# A-Power.net
KiCad netlist of a schematic drawn in Altium Designer
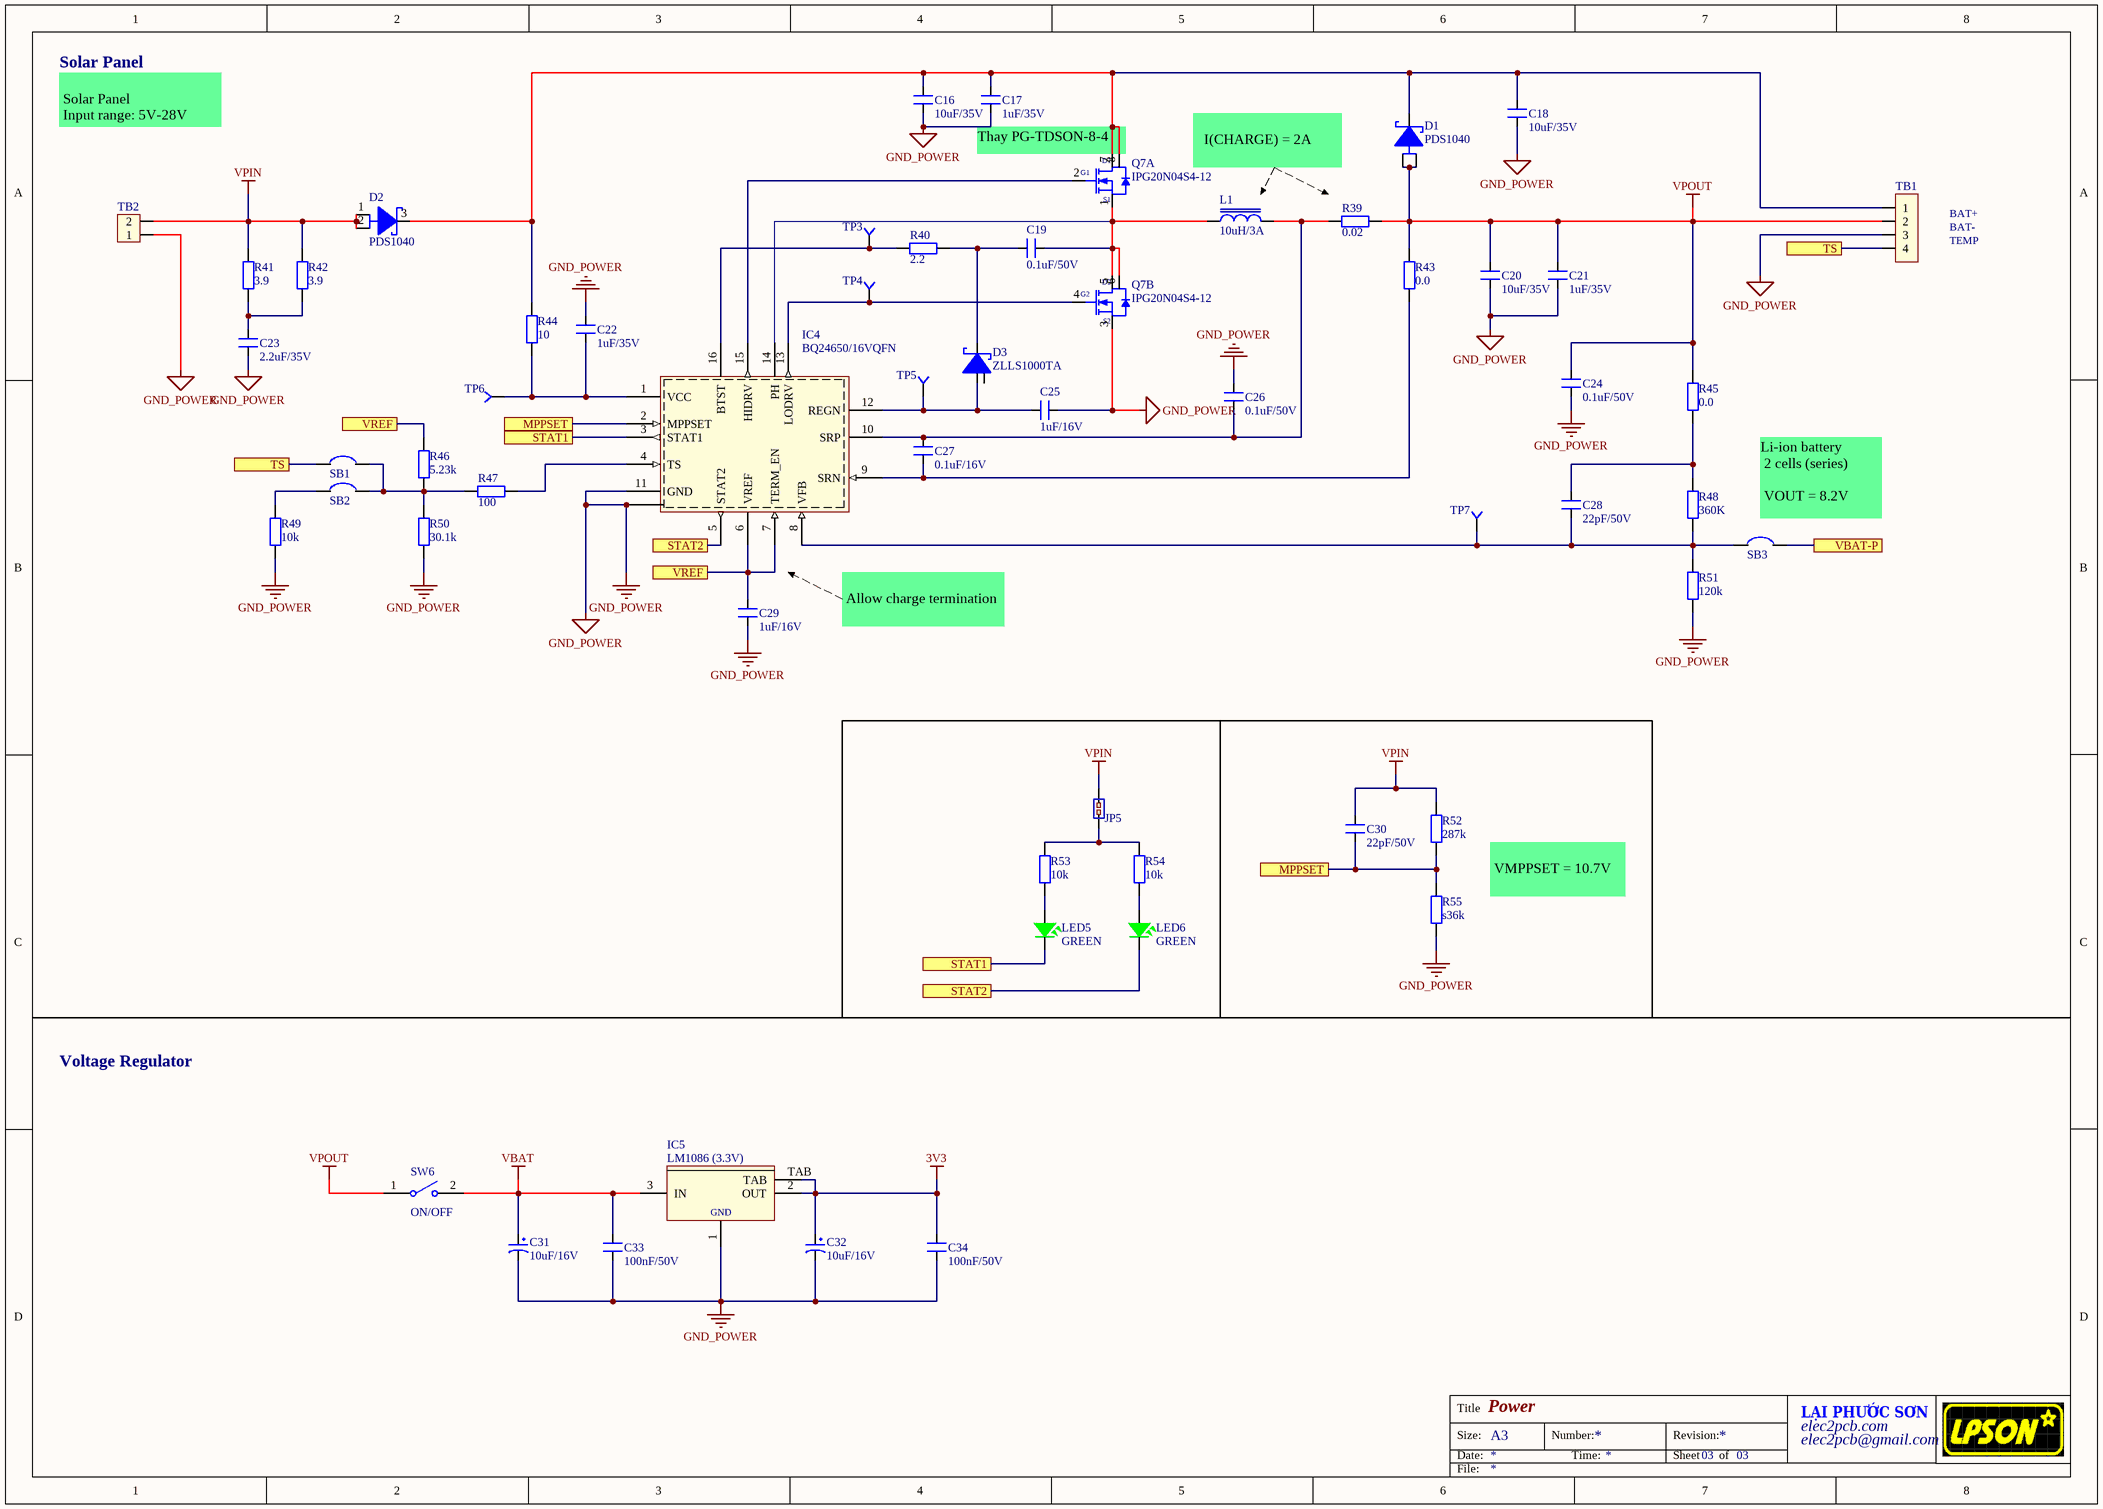
[diagram p0: A-Power.SchDoc]

(export (version "E")
  (design (tool "Eeschema 10.0.6"))
  (components
    (comp (ref "C16")
      (value "10uF/35V")
      (footprint "CAP_CERA_C3216(CC1206INCH)")
      (description "CAP CER 10UF 35V X7R 1206")
      (fields
        (field (name "MANUFACTURER") "Taiyo Yuden")
        (field (name "MANUFACTURER PART NUMBER") "GMK316AB7106KL-TR")
      )
      (libsource (lib "Tran Tuan") (part "CAP-CER/10uF/35V/X7R-1206"))
    )
    (comp (ref "C17")
      (value "1uF/35V")
      (footprint "CAP_CERA_C2012(CC0805INCH)")
      (description "CAP CER 1UF 35V X7R 0805")
      (fields
        (field (name "MANUFACTURER") "Taiyo Yuden")
        (field (name "MANUFACTURER PART NUMBER") "GMK212B7105KG-T")
      )
      (libsource (lib "Tran Tuan") (part "CAP-CER/1uF/35V/X7R/0805"))
    )
    (comp (ref "C18")
      (value "10uF/35V")
      (footprint "CAP_CERA_C3216(CC1206INCH)")
      (description "CAP CER 10UF 35V X7R 1206")
      (fields
        (field (name "MANUFACTURER") "Taiyo Yuden")
        (field (name "MANUFACTURER PART NUMBER") "GMK316AB7106KL-TR")
      )
      (libsource (lib "Tran Tuan") (part "CAP-CER/10uF/35V/X7R-1206"))
    )
    (comp (ref "C19")
      (value "0.1uF/50V")
      (footprint "CAP_CERA_C1608(CC0603INCH)")
      (description "CAP CER 0.1UF 50V X7R 0603")
      (fields
        (field (name "MANUFACTURER") "Kemet")
        (field (name "MANUFACTURER PART NUMBER") "C0603X104K5RACTU")
      )
      (libsource (lib "Tran Tuan") (part "CAP-CER/0.1uF/50V/X7R/0603"))
    )
    (comp (ref "C20")
      (value "10uF/35V")
      (footprint "CAP_CERA_C3216(CC1206INCH)")
      (description "CAP CER 10UF 35V X7R 1206")
      (fields
        (field (name "MANUFACTURER") "Taiyo Yuden")
        (field (name "MANUFACTURER PART NUMBER") "GMK316AB7106KL-TR")
      )
      (libsource (lib "Tran Tuan") (part "CAP-CER/10uF/35V/X7R-1206"))
    )
    (comp (ref "C21")
      (value "1uF/35V")
      (footprint "CAP_CERA_C2012(CC0805INCH)")
      (description "CAP CER 1UF 35V X7R 0805")
      (fields
        (field (name "MANUFACTURER") "Taiyo Yuden")
        (field (name "MANUFACTURER PART NUMBER") "GMK212B7105KG-T")
      )
      (libsource (lib "Tran Tuan") (part "CAP-CER/1uF/35V/X7R/0805"))
    )
    (comp (ref "C22")
      (value "1uF/35V")
      (footprint "CAP_CERA_C2012(CC0805INCH)")
      (description "CAP CER 1UF 35V X7R 0805")
      (fields
        (field (name "MANUFACTURER") "Taiyo Yuden")
        (field (name "MANUFACTURER PART NUMBER") "GMK212B7105KG-T")
      )
      (libsource (lib "Tran Tuan") (part "CAP-CER/1uF/35V/X7R/0805"))
    )
    (comp (ref "C23")
      (value "2.2uF/35V")
      (footprint "CAP_CERA_C3225(CC1210)")
      (description "CAP CER 2.2UF 35V X7R 1210")
      (fields
        (field (name "MANUFACTURER") "Taiyo Yuden")
        (field (name "MANUFACTURER PART NUMBER") "GMK325B7225KNHT")
      )
      (libsource (lib "Tran Tuan") (part "CAP-CER/2.2uF/35V/X7R/1210"))
    )
    (comp (ref "C24")
      (value "0.1uF/50V")
      (footprint "CAP_CERA_C1608(CC0603INCH)")
      (description "CAP CER 0.1UF 50V X7R 0603")
      (fields
        (field (name "MANUFACTURER") "Kemet")
        (field (name "MANUFACTURER PART NUMBER") "C0603X104K5RACTU")
      )
      (libsource (lib "Tran Tuan") (part "CAP-CER/0.1uF/50V/X7R/0603"))
    )
    (comp (ref "C25")
      (value "1uF/16V")
      (footprint "CAP_CERA_C2012(CC0805INCH)")
      (description "CAP CER 1UF 16V X7R 0805")
      (fields
        (field (name "MANUFACTURER") "Kemet")
        (field (name "MANUFACTURER PART NUMBER") "C0805C105K4RACTU")
      )
      (libsource (lib "Tran Tuan") (part "CAP-CER/1uF/16V/X7R/0805"))
    )
    (comp (ref "C26")
      (value "0.1uF/50V")
      (footprint "CAP_CERA_C1608(CC0603INCH)")
      (description "CAP CER 0.1UF 50V X7R 0603")
      (fields
        (field (name "MANUFACTURER") "Kemet")
        (field (name "MANUFACTURER PART NUMBER") "C0603X104K5RACTU")
      )
      (libsource (lib "Tran Tuan") (part "CAP-CER/0.1uF/50V/X7R/0603"))
    )
    (comp (ref "C27")
      (value "0.1uF/16V")
      (footprint "CAP_CERA_C1608(CC0603INCH)")
      (description "CAP CER 0.1UF 16V X7R 0603")
      (fields
        (field (name "MANUFACTURER") "Yageo")
        (field (name "MANUFACTURER PART NUMBER") "CC0603KRX7R7BB104")
      )
      (libsource (lib "Tran Tuan") (part "CAP-CER/0.1uF/16V/X7R/0603"))
    )
    (comp (ref "C28")
      (value "22pF/50V")
      (footprint "CAP_CERA_C1608(CC0603INCH)")
      (description "CAP CER 22PF 50V X7R 0603")
      (fields
        (field (name "MANUFACTURER") "AVX Corporation")
        (field (name "MANUFACTURER PART NUMBER") "06035C220JAT2A")
      )
      (libsource (lib "Tran Tuan") (part "CAP-CER/22pF/50V/X7R/0603"))
    )
    (comp (ref "C29")
      (value "1uF/16V")
      (footprint "CAP_CERA_C2012(CC0805INCH)")
      (description "CAP CER 1UF 16V X7R 0805")
      (fields
        (field (name "MANUFACTURER") "Kemet")
        (field (name "MANUFACTURER PART NUMBER") "C0805C105K4RACTU")
      )
      (libsource (lib "Tran Tuan") (part "CAP-CER/1uF/16V/X7R/0805"))
    )
    (comp (ref "C30")
      (value "22pF/50V")
      (footprint "CAP_CERA_C1608(CC0603INCH)")
      (description "CAP CER 22PF 50V X7R 0603")
      (fields
        (field (name "MANUFACTURER") "AVX Corporation")
        (field (name "MANUFACTURER PART NUMBER") "06035C220JAT2A")
      )
      (libsource (lib "Tran Tuan") (part "CAP-CER/22pF/50V/X7R/0603"))
    )
    (comp (ref "C31")
      (value "10uF/16V")
      (footprint "CAP_CERA_C3216(CC1206INCH)")
      (description "CAP TANT 10UF 16V 10% 1206")
      (fields
        (field (name "MANUFACTURER") "Kemet")
        (field (name "MANUFACTURER PART NUMBER") "T491A106K016AT")
      )
      (libsource (lib "Tran Tuan") (part "CAP-TANT/10uF/16V/1206"))
    )
    (comp (ref "C32")
      (value "10uF/16V")
      (footprint "CAP_CERA_C3216(CC1206INCH)")
      (description "CAP TANT 10UF 16V 10% 1206")
      (fields
        (field (name "MANUFACTURER") "Kemet")
        (field (name "MANUFACTURER PART NUMBER") "T491A106K016AT")
      )
      (libsource (lib "Tran Tuan") (part "CAP-TANT/10uF/16V/1206"))
    )
    (comp (ref "C33")
      (value "100nF/50V")
      (footprint "CAP_CERA_C2012(CC0805INCH)")
      (description "CAP CER 0.1UF 50V X7R 0805")
      (fields
        (field (name "MANUFACTURER") "AVX Corporation")
        (field (name "MANUFACTURER PART NUMBER") "08055C104KAT2A")
      )
      (libsource (lib "Tran Tuan") (part "CAP-CER/100nF/50V/X7R-0805"))
    )
    (comp (ref "C34")
      (value "100nF/50V")
      (footprint "CAP_CERA_C2012(CC0805INCH)")
      (description "CAP CER 0.1UF 50V X7R 0805")
      (fields
        (field (name "MANUFACTURER") "AVX Corporation")
        (field (name "MANUFACTURER PART NUMBER") "08055C104KAT2A")
      )
      (libsource (lib "Tran Tuan") (part "CAP-CER/100nF/50V/X7R-0805"))
    )
    (comp (ref "D1")
      (value "PDS1040")
      (footprint "PDS1040")
      (description "DIODE SCHOTTKY 40V 10A POWERDI5")
      (fields
        (field (name "MANUFACTURER") "Diodes Incorporated")
        (field (name "MANUFACTURER PART NUMBER") "PDS1040-13")
      )
      (libsource (lib "Tran Tuan") (part "DIODE-PDS1040/POWERDI5"))
    )
    (comp (ref "D2")
      (value "PDS1040")
      (footprint "PDS1040")
      (description "DIODE SCHOTTKY 40V 10A POWERDI5")
      (fields
        (field (name "MANUFACTURER") "Diodes Incorporated")
        (field (name "MANUFACTURER PART NUMBER") "PDS1040-13")
      )
      (libsource (lib "") (part "DIODE-PDS1040/POWERDI5_1"))
    )
    (comp (ref "D3")
      (value "ZLLS1000TA")
      (footprint "ZLLS1000")
      (description "DIODE SCHOTTKY 40V 1.16A SOT23-3")
      (fields (field (name "MANUFACTURER") "Diodes Incorporated"))
      (libsource (lib "Tran Tuan") (part "DIODE-ZLLS1000TA/SOT23-3"))
    )
    (comp (ref "IC4")
      (value "BQ24650/16VQFN")
      (footprint "BQ24650-16VQFN")
      (description "IC SYNC SW-MODE BAT CHRGR 16VQFN")
      (fields
        (field (name "MANUFACTURER") "Texas Instruments")
        (field (name "MANUFACTURER PART NUMBER") "BQ24650RVAT")
      )
      (libsource (lib "Tran Tuan") (part "BQ24650/16VQFN"))
    )
    (comp (ref "IC5")
      (value "LM1086 (3.3V)")
      (footprint "LM1086")
      (description "IC REG LDO 3.3V 1.5A DDPAK")
      (fields
        (field (name "MANUFACTURER") "Texas Instruments")
        (field (name "MANUFACTURER PART NUMBER") "LM1086CS-3.3/NOPB")
      )
      (libsource (lib "Tran Tuan") (part "LM1086CS-3.3/NOPB"))
    )
    (comp (ref "JP5")
      (value "JP2-ShortingJumper")
      (footprint "Header_2")
      (description "2.54mm 2-Pin Shorting Jumper")
      (libsource (lib "Tran Tuan") (part "JP2-ShortingJumper"))
    )
    (comp (ref "L1")
      (value "10uH/3A")
      (footprint "IHLP-2525CZ-01")
      (description "FIXED IND 10UH 3A 105mOHM SMD")
      (fields
        (field (name "MANUFACTURER") "Vishay Dale")
        (field (name "MANUFACTURER PART NUMBER") "IHLP2525CZER100M01")
      )
      (libsource (lib "Tran Tuan") (part "IND-10uH/3A/105mOHM"))
    )
    (comp (ref "LED5")
      (value "GREEN")
      (footprint "Led 0805G")
      (description "LED GREEN CLEAR 0805 SMD")
      (fields
        (field (name "MANUFACTURER") "Lite-On Inc.")
        (field (name "MANUFACTURER PART NUMBER") "LTST-C171GKT")
      )
      (libsource (lib "Tran Tuan") (part "LED-GREEN/CLEAR/0805"))
    )
    (comp (ref "LED6")
      (value "GREEN")
      (footprint "Led 0805G")
      (description "LED GREEN CLEAR 0805 SMD")
      (fields
        (field (name "MANUFACTURER") "Lite-On Inc.")
        (field (name "MANUFACTURER PART NUMBER") "LTST-C171GKT")
      )
      (libsource (lib "Tran Tuan") (part "LED-GREEN/CLEAR/0805"))
    )
    (comp (ref "Q7")
      (value "IPG20N04S4-12")
      (footprint "PG-TDSON-8-4")
      (description "MOSFE,T 2N-CH, 40V 20A TDSON-8 OptiMOS-T2")
      (fields (field (name "MANUFACTURER") "Infineon"))
      (libsource (lib "Tran Tuan") (part "MOSFET-IPG20N04S4/TDSON8"))
    )
    (comp (ref "R39")
      (value "~")
      (footprint "RES-1206-3216MM")
      (description "RES SMD 0.02 OHM 1% 1W 1206")
      (fields
        (field (name "MANUFACTURER") "Vishay Dale")
        (field (name "MANUFACTURER PART NUMBER") "WSLP1206R0200FEA")
        (field (name "RESISTANCE (OHMS)") "0.02")
      )
      (libsource (lib "Tran Tuan") (part "RES-1206/±1%"))
    )
    (comp (ref "R40")
      (value "~")
      (footprint "RESC2012(0805)")
      (description "RES SMD 2.2 OHM 5% 1/8W 0805")
      (fields
        (field (name "MANUFACTURER") "Panasonic Electronic Components")
        (field (name "MANUFACTURER PART NUMBER") "ERJ-6GEYJ2R2V")
        (field (name "RESISTANCE (OHMS)") "2.2")
      )
      (libsource (lib "Tran Tuan") (part "RES-0805/±5%"))
    )
    (comp (ref "R41")
      (value "~")
      (footprint "RES-1206-3216MM")
      (description "RES SMD 3.9 OHM 1% 1/4W 1206")
      (fields
        (field (name "MANUFACTURER") "Panasonic Electronic Components")
        (field (name "MANUFACTURER PART NUMBER") "ERJ-8RQF3R9V")
        (field (name "RESISTANCE (OHMS)") "3.9")
      )
      (libsource (lib "Tran Tuan") (part "RES-1206/±5%"))
    )
    (comp (ref "R42")
      (value "~")
      (footprint "RES-1206-3216MM")
      (description "RES SMD 3.9 OHM 1% 1/4W 1206")
      (fields
        (field (name "MANUFACTURER") "Panasonic Electronic Components")
        (field (name "MANUFACTURER PART NUMBER") "ERJ-8RQF3R9V")
        (field (name "RESISTANCE (OHMS)") "3.9")
      )
      (libsource (lib "Tran Tuan") (part "RES-1206/±5%"))
    )
    (comp (ref "R43")
      (value "~")
      (footprint "RESC2012(0805)")
      (description "RES SMD 0.0 OHM JUMPER 1/8W 0805")
      (fields
        (field (name "MANUFACTURER") "Yageo")
        (field (name "MANUFACTURER PART NUMBER") "RC0805JR-070RL")
        (field (name "RESISTANCE (OHMS)") "0.0")
      )
      (libsource (lib "") (part "RES-0805/±5%_1"))
    )
    (comp (ref "R44")
      (value "~")
      (footprint "RESC2012(0805)")
      (description "RES SMD 10 OHM 5% 1/8W 0805")
      (fields
        (field (name "MANUFACTURER") "Yageo")
        (field (name "MANUFACTURER PART NUMBER") "RC0805JR-0710RL")
        (field (name "RESISTANCE (OHMS)") "10")
      )
      (libsource (lib "") (part "RES-0805/±5%_1"))
    )
    (comp (ref "R45")
      (value "~")
      (footprint "RESC2012(0805)")
      (description "RES SMD 0.0 OHM JUMPER 1/8W 0805")
      (fields
        (field (name "MANUFACTURER") "Yageo")
        (field (name "MANUFACTURER PART NUMBER") "RC0805JR-070RL")
        (field (name "RESISTANCE (OHMS)") "0.0")
      )
      (libsource (lib "") (part "RES-0805/±5%_1"))
    )
    (comp (ref "R46")
      (value "~")
      (footprint "RESC2012(0805)")
      (description "RES SMD 5.23K OHM 1% 1/8W 0805")
      (fields
        (field (name "MANUFACTURER") "Panasonic Electronic Components")
        (field (name "MANUFACTURER PART NUMBER") "ERJ-6ENF5231V")
        (field (name "RESISTANCE (OHMS)") "5.23k")
      )
      (libsource (lib "Tran Tuan") (part "RES-0805/±1%"))
    )
    (comp (ref "R47")
      (value "~")
      (footprint "RESC2012(0805)")
      (description "RES SMD 100 OHM 5% 1/8W 0805")
      (fields
        (field (name "MANUFACTURER") "Panasonic Electronic Components")
        (field (name "MANUFACTURER PART NUMBER") "ERJ-6GEYJ101V")
        (field (name "RESISTANCE (OHMS)") "100")
      )
      (libsource (lib "Tran Tuan") (part "RES-0805/±5%"))
    )
    (comp (ref "R48")
      (value "360K")
      (footprint "RESC2012(0805)")
      (description "RES SMD 360K OHM 1% 1/8W 0805")
      (fields
        (field (name "MANUFACTURER") "Yageo")
        (field (name "MANUFACTURER PART NUMBER") "RC0805FR-07360KL")
      )
      (libsource (lib "") (part "RES-0805/±1%_1"))
    )
    (comp (ref "R49")
      (value "~")
      (footprint "RESC2012(0805)")
      (description "RES SMD 10K OHM 5% 1/8W 0805")
      (fields
        (field (name "MANUFACTURER") "Yageo")
        (field (name "MANUFACTURER PART NUMBER") "RC0805JR-0710KL")
        (field (name "RESISTANCE (OHMS)") "10k")
      )
      (libsource (lib "") (part "RES-0805/±5%_1"))
    )
    (comp (ref "R50")
      (value "~")
      (footprint "RESC2012(0805)")
      (description "RES SMD 30.1K OHM 1% 1/8W 0805")
      (fields
        (field (name "MANUFACTURER") "Yageo")
        (field (name "MANUFACTURER PART NUMBER") "RC0805FR-0730K1L")
        (field (name "RESISTANCE (OHMS)") "30.1k")
      )
      (libsource (lib "Tran Tuan") (part "RES-0805/±1%"))
    )
    (comp (ref "R51")
      (value "~")
      (footprint "RESC2012(0805)")
      (description "RES SMD 120K OHM 1% 1/8W 0805")
      (fields
        (field (name "MANUFACTURER") "Yageo")
        (field (name "MANUFACTURER PART NUMBER") "RC0805FR-07120KL")
        (field (name "RESISTANCE (OHMS)") "120k")
      )
      (libsource (lib "Tran Tuan") (part "RES-0805/±1%"))
    )
    (comp (ref "R52")
      (value "~")
      (footprint "RESC2012(0805)")
      (description "RES SMD 287K OHM 1% 1/8W 0805")
      (fields
        (field (name "MANUFACTURER") "Panasonic Electronic Components")
        (field (name "MANUFACTURER PART NUMBER") "ERJ-6ENF2873V")
        (field (name "RESISTANCE (OHMS)") "287k")
      )
      (libsource (lib "Tran Tuan") (part "RES-0805/±1%"))
    )
    (comp (ref "R53")
      (value "~")
      (footprint "RESC2012(0805)")
      (description "RES SMD 10K OHM 5% 1/8W 0805")
      (fields
        (field (name "MANUFACTURER") "Yageo")
        (field (name "MANUFACTURER PART NUMBER") "RC0805JR-0710KL")
        (field (name "RESISTANCE (OHMS)") "10k")
      )
      (libsource (lib "") (part "RES-0805/±5%_1"))
    )
    (comp (ref "R54")
      (value "~")
      (footprint "RESC2012(0805)")
      (description "RES SMD 10K OHM 5% 1/8W 0805")
      (fields
        (field (name "MANUFACTURER") "Yageo")
        (field (name "MANUFACTURER PART NUMBER") "RC0805JR-0710KL")
        (field (name "RESISTANCE (OHMS)") "10k")
      )
      (libsource (lib "") (part "RES-0805/±5%_1"))
    )
    (comp (ref "R55")
      (value "~")
      (footprint "RESC2012(0805)")
      (description "RES SMD 36K OHM 1% 1/8W 0805")
      (fields
        (field (name "MANUFACTURER") "Panasonic Electronic Components")
        (field (name "MANUFACTURER PART NUMBER") "ERJ-6ENF3602V")
        (field (name "RESISTANCE (OHMS)") "s36k")
      )
      (libsource (lib "") (part "RES-0805/±1%_1"))
    )
    (comp (ref "SB1")
      (value "Connect")
      (footprint "head PAD")
      (description "Jumper, Connector, 2-pad")
      (libsource (lib "Tran Tuan") (part "Connector-SB"))
    )
    (comp (ref "SB2")
      (value "Connect")
      (footprint "head PAD")
      (description "Jumper, Connector, 2-pad")
      (libsource (lib "Tran Tuan") (part "Connector-SB"))
    )
    (comp (ref "SB3")
      (value "Connect")
      (footprint "head PAD")
      (description "Jumper, Connector, 2-pad")
      (libsource (lib "Tran Tuan") (part "Connector-SB"))
    )
    (comp (ref "SW6")
      (value "ON/OFF")
      (footprint "SW-POWER")
      (description "SWITCH ROCKER SPST 16A 125V")
      (fields
        (field (name "MANUFACTURER") "TE Connectivity Alcoswitch Switches")
        (field (name "MANUFACTURER PART NUMBER") "PRASA1-16F-BB0BW")
      )
      (libsource (lib "Tran Tuan") (part "SW-ROCKER/SPST/16A"))
    )
    (comp (ref "TB1")
      (value "TERM BLOCK")
      (footprint "MKDS-DOMINO-4-PIN")
      (description "TERM BLOCK 4POS 3.81MM PCB GRN")
      (fields
        (field (name "MANUFACTURER") "Phoenix Contact")
        (field (name "MANUFACTURER PART NUMBER") "1727036")
      )
      (libsource (lib "Tran Tuan") (part "TERM/3.81MM/4POS/GREEN"))
    )
    (comp (ref "TB2")
      (value "TERM BLOCK")
      (footprint "MKDS-DOMINO-2-PIN")
      (description "TERM BLOCK 2POS 3.81MM PCB GRN")
      (fields
        (field (name "MANUFACTURER") "Phoenix Contact")
        (field (name "MANUFACTURER PART NUMBER") "1727010")
      )
      (libsource (lib "Tran Tuan") (part "TERM/3.81MM/2POS/GREEN"))
    )
    (comp (ref "TP3")
      (value "Test Point")
      (footprint "Test_point_VIA06")
      (description "Test Point, Pad, Hole")
      (libsource (lib "Tran Tuan") (part "Connector-TP"))
    )
    (comp (ref "TP4")
      (value "Test Point")
      (footprint "Test_point_VIA06")
      (description "Test Point, Pad, Hole")
      (libsource (lib "Tran Tuan") (part "Connector-TP"))
    )
    (comp (ref "TP5")
      (value "Test Point")
      (footprint "Test_point_VIA06")
      (description "Test Point, Pad, Hole")
      (libsource (lib "Tran Tuan") (part "Connector-TP"))
    )
    (comp (ref "TP6")
      (value "Test Point")
      (footprint "Test_point_VIA06")
      (description "Test Point, Pad, Hole")
      (libsource (lib "Tran Tuan") (part "Connector-TP"))
    )
    (comp (ref "TP7")
      (value "Test Point")
      (footprint "Test_point_VIA06")
      (description "Test Point, Pad, Hole")
      (libsource (lib "Tran Tuan") (part "Connector-TP"))
    )
  )
  (nets
    (net (code "1") (name "/MPPSET") (class "Default")
      (node (ref "C30") (pin "2") (pinfunction "2_2") (pintype "passive"))
      (node (ref "IC4") (pin "2") (pinfunction "MPPSET_2") (pintype "input"))
      (node (ref "R52") (pin "2") (pinfunction "2_2") (pintype "passive"))
      (node (ref "R55") (pin "2") (pinfunction "2_2") (pintype "passive"))
    )
    (net (code "2") (name "/STAT1") (class "Default")
      (node (ref "IC4") (pin "3") (pinfunction "STAT1_3") (pintype "output"))
      (node (ref "LED5") (pin "2") (pinfunction "K_2") (pintype "passive"))
    )
    (net (code "3") (name "/STAT2") (class "Default")
      (node (ref "IC4") (pin "5") (pinfunction "STAT2_5") (pintype "output"))
      (node (ref "LED6") (pin "2") (pinfunction "K_2") (pintype "passive"))
    )
    (net (code "4") (name "/TS") (class "Default")
      (node (ref "SB1") (pin "2") (pinfunction "2_2") (pintype "passive"))
      (node (ref "TB1") (pin "4") (pinfunction "4_4") (pintype "passive"))
    )
    (net (code "5") (name "/VBAT-P") (class "Default")
      (node (ref "SB3") (pin "1") (pinfunction "1_1") (pintype "passive"))
    )
    (net (code "6") (name "/VREF") (class "Default")
      (node (ref "C29") (pin "2") (pinfunction "2_2") (pintype "passive"))
      (node (ref "IC4") (pin "6") (pinfunction "VREF_6") (pintype "power_in"))
      (node (ref "IC4") (pin "7") (pinfunction "TERM_EN_7") (pintype "input"))
      (node (ref "R46") (pin "1") (pinfunction "1_1") (pintype "passive"))
    )
    (net (code "7") (name "3V3") (class "Default")
      (node (ref "C32") (pin "1") (pinfunction "1_1") (pintype "passive"))
      (node (ref "C34") (pin "1") (pinfunction "1_1") (pintype "passive"))
      (node (ref "IC5") (pin "2") (pinfunction "OUT_2") (pintype "power_in"))
      (node (ref "IC5") (pin "TAB") (pinfunction "TAB_TAB") (pintype "power_in"))
    )
    (net (code "8") (name "GND_POWER") (class "Default")
      (node (ref "C16") (pin "2") (pinfunction "2_2") (pintype "passive"))
      (node (ref "C17") (pin "2") (pinfunction "2_2") (pintype "passive"))
      (node (ref "C18") (pin "2") (pinfunction "2_2") (pintype "passive"))
      (node (ref "C20") (pin "2") (pinfunction "2_2") (pintype "passive"))
      (node (ref "C21") (pin "2") (pinfunction "2_2") (pintype "passive"))
      (node (ref "C22") (pin "2") (pinfunction "2_2") (pintype "passive"))
      (node (ref "C23") (pin "2") (pinfunction "2_2") (pintype "passive"))
      (node (ref "C24") (pin "1") (pinfunction "1_1") (pintype "passive"))
      (node (ref "C25") (pin "1") (pinfunction "1_1") (pintype "passive"))
      (node (ref "C26") (pin "2") (pinfunction "2_2") (pintype "passive"))
      (node (ref "C29") (pin "1") (pinfunction "1_1") (pintype "passive"))
      (node (ref "C31") (pin "2") (pinfunction "2_2") (pintype "passive"))
      (node (ref "C32") (pin "2") (pinfunction "2_2") (pintype "passive"))
      (node (ref "C33") (pin "2") (pinfunction "2_2") (pintype "passive"))
      (node (ref "C34") (pin "2") (pinfunction "2_2") (pintype "passive"))
      (node (ref "IC4") (pin "11") (pinfunction "GND_11") (pintype "power_in"))
      (node (ref "IC4") (pin "PAD") (pinfunction "PAD_PAD") (pintype "power_in"))
      (node (ref "IC5") (pin "1") (pinfunction "GND_1") (pintype "power_in"))
      (node (ref "Q7") (pin "3") (pinfunction "S2_3") (pintype "passive"))
      (node (ref "R49") (pin "2") (pinfunction "2_2") (pintype "passive"))
      (node (ref "R50") (pin "2") (pinfunction "2_2") (pintype "passive"))
      (node (ref "R51") (pin "2") (pinfunction "2_2") (pintype "passive"))
      (node (ref "R55") (pin "1") (pinfunction "1_1") (pintype "passive"))
      (node (ref "TB1") (pin "3") (pinfunction "3_3") (pintype "passive"))
      (node (ref "TB2") (pin "1") (pinfunction "1_1") (pintype "passive"))
    )
    (net (code "9") (name "Net-(C23-Pad1)") (class "Default")
      (node (ref "C23") (pin "1") (pinfunction "1_1") (pintype "passive"))
      (node (ref "R41") (pin "2") (pinfunction "2_2") (pintype "passive"))
      (node (ref "R42") (pin "2") (pinfunction "2_2") (pintype "passive"))
    )
    (net (code "10") (name "Net-(C28-Pad1)") (class "Default")
      (node (ref "C28") (pin "1") (pinfunction "1_1") (pintype "passive"))
      (node (ref "R45") (pin "2") (pinfunction "2_2") (pintype "passive"))
      (node (ref "R48") (pin "2") (pinfunction "2_2") (pintype "passive"))
    )
    (net (code "11") (name "Net-(D1-K)") (class "Default")
      (node (ref "C16") (pin "1") (pinfunction "1_1") (pintype "passive"))
      (node (ref "C17") (pin "1") (pinfunction "1_1") (pintype "passive"))
      (node (ref "C18") (pin "1") (pinfunction "1_1") (pintype "passive"))
      (node (ref "D1") (pin "3") (pinfunction "K_3") (pintype "passive"))
      (node (ref "D2") (pin "3") (pinfunction "K_3") (pintype "passive"))
      (node (ref "Q7") (pin "7") (pinfunction "D1_7") (pintype "passive"))
      (node (ref "Q7") (pin "8") (pinfunction "D1_8") (pintype "passive"))
      (node (ref "R44") (pin "1") (pinfunction "1_1") (pintype "passive"))
      (node (ref "TB1") (pin "1") (pinfunction "1_1") (pintype "passive"))
    )
    (net (code "12") (name "Net-(D3-A)") (class "Default")
      (node (ref "C25") (pin "2") (pinfunction "2_2") (pintype "passive"))
      (node (ref "D3") (pin "1") (pinfunction "A_1") (pintype "passive"))
      (node (ref "IC4") (pin "12") (pinfunction "REGN_12") (pintype "power_in"))
      (node (ref "TP5") (pin "1") (pinfunction "1_1") (pintype "passive"))
    )
    (net (code "13") (name "Net-(D3-K)") (class "Default")
      (node (ref "C19") (pin "1") (pinfunction "1_1") (pintype "passive"))
      (node (ref "D3") (pin "3") (pinfunction "K_3") (pintype "passive"))
      (node (ref "R40") (pin "2") (pinfunction "2_2") (pintype "passive"))
    )
    (net (code "14") (name "Net-(IC4-BTST)") (class "Default")
      (node (ref "IC4") (pin "16") (pinfunction "BTST_16") (pintype "power_in"))
      (node (ref "R40") (pin "1") (pinfunction "1_1") (pintype "passive"))
      (node (ref "TP3") (pin "1") (pinfunction "1_1") (pintype "passive"))
    )
    (net (code "15") (name "Net-(IC4-HIDRV)") (class "Default")
      (node (ref "IC4") (pin "15") (pinfunction "HIDRV_15") (pintype "output"))
      (node (ref "Q7") (pin "2") (pinfunction "G1_2") (pintype "passive"))
    )
    (net (code "16") (name "Net-(IC4-LODRV)") (class "Default")
      (node (ref "IC4") (pin "13") (pinfunction "LODRV_13") (pintype "output"))
      (node (ref "Q7") (pin "4") (pinfunction "G2_4") (pintype "passive"))
      (node (ref "TP4") (pin "1") (pinfunction "1_1") (pintype "passive"))
    )
    (net (code "17") (name "Net-(IC4-PH)") (class "Default")
      (node (ref "C19") (pin "2") (pinfunction "2_2") (pintype "passive"))
      (node (ref "IC4") (pin "14") (pinfunction "PH_14") (pintype "power_in"))
      (node (ref "L1") (pin "1") (pinfunction "1_1") (pintype "passive"))
      (node (ref "Q7") (pin "1") (pinfunction "S1_1") (pintype "passive"))
      (node (ref "Q7") (pin "5") (pinfunction "D2_5") (pintype "passive"))
      (node (ref "Q7") (pin "6") (pinfunction "D2_6") (pintype "passive"))
    )
    (net (code "18") (name "Net-(IC4-SRN)") (class "Default")
      (node (ref "C27") (pin "2") (pinfunction "2_2") (pintype "passive"))
      (node (ref "IC4") (pin "9") (pinfunction "SRN_9") (pintype "input"))
      (node (ref "R43") (pin "2") (pinfunction "2_2") (pintype "passive"))
    )
    (net (code "19") (name "Net-(IC4-SRP)") (class "Default")
      (node (ref "C26") (pin "1") (pinfunction "1_1") (pintype "passive"))
      (node (ref "C27") (pin "1") (pinfunction "1_1") (pintype "passive"))
      (node (ref "IC4") (pin "10") (pinfunction "SRP_10") (pintype "passive"))
      (node (ref "L1") (pin "2") (pinfunction "2_2") (pintype "passive"))
      (node (ref "R39") (pin "1") (pinfunction "1_1") (pintype "passive"))
    )
    (net (code "20") (name "Net-(IC4-TS)") (class "Default")
      (node (ref "IC4") (pin "4") (pinfunction "TS_4") (pintype "input"))
      (node (ref "R47") (pin "2") (pinfunction "2_2") (pintype "passive"))
    )
    (net (code "21") (name "Net-(IC4-VCC)") (class "Default")
      (node (ref "C22") (pin "1") (pinfunction "1_1") (pintype "passive"))
      (node (ref "IC4") (pin "1") (pinfunction "VCC_1") (pintype "power_in"))
      (node (ref "R44") (pin "2") (pinfunction "2_2") (pintype "passive"))
      (node (ref "TP6") (pin "1") (pinfunction "1_1") (pintype "passive"))
    )
    (net (code "22") (name "Net-(IC4-VFB)") (class "Default")
      (node (ref "C28") (pin "2") (pinfunction "2_2") (pintype "passive"))
      (node (ref "IC4") (pin "8") (pinfunction "VFB_8") (pintype "input"))
      (node (ref "R48") (pin "1") (pinfunction "1_1") (pintype "passive"))
      (node (ref "R51") (pin "1") (pinfunction "1_1") (pintype "passive"))
      (node (ref "SB3") (pin "2") (pinfunction "2_2") (pintype "passive"))
      (node (ref "TP7") (pin "1") (pinfunction "1_1") (pintype "passive"))
    )
    (net (code "23") (name "Net-(JP5-Pad1)") (class "Default")
      (node (ref "JP5") (pin "1") (pinfunction "1_1") (pintype "passive"))
      (node (ref "R53") (pin "1") (pinfunction "1_1") (pintype "passive"))
      (node (ref "R54") (pin "1") (pinfunction "1_1") (pintype "passive"))
    )
    (net (code "24") (name "Net-(LED5-A)") (class "Default")
      (node (ref "LED5") (pin "1") (pinfunction "A_1") (pintype "passive"))
      (node (ref "R53") (pin "2") (pinfunction "2_2") (pintype "passive"))
    )
    (net (code "25") (name "Net-(LED6-A)") (class "Default")
      (node (ref "LED6") (pin "1") (pinfunction "A_1") (pintype "passive"))
      (node (ref "R54") (pin "2") (pinfunction "2_2") (pintype "passive"))
    )
    (net (code "26") (name "Net-(R46-Pad2)") (class "Default")
      (node (ref "R46") (pin "2") (pinfunction "2_2") (pintype "passive"))
      (node (ref "R47") (pin "1") (pinfunction "1_1") (pintype "passive"))
      (node (ref "R50") (pin "1") (pinfunction "1_1") (pintype "passive"))
      (node (ref "SB1") (pin "1") (pinfunction "1_1") (pintype "passive"))
      (node (ref "SB2") (pin "1") (pinfunction "1_1") (pintype "passive"))
    )
    (net (code "27") (name "Net-(R49-Pad1)") (class "Default")
      (node (ref "R49") (pin "1") (pinfunction "1_1") (pintype "passive"))
      (node (ref "SB2") (pin "2") (pinfunction "2_2") (pintype "passive"))
    )
    (net (code "28") (name "VBAT") (class "Default")
      (node (ref "C31") (pin "1") (pinfunction "1_1") (pintype "passive"))
      (node (ref "C33") (pin "1") (pinfunction "1_1") (pintype "passive"))
      (node (ref "IC5") (pin "3") (pinfunction "IN_3") (pintype "power_in"))
      (node (ref "SW6") (pin "2") (pinfunction "2_2") (pintype "passive"))
    )
    (net (code "29") (name "VPIN") (class "Default")
      (node (ref "C30") (pin "1") (pinfunction "1_1") (pintype "passive"))
      (node (ref "D2") (pin "1") (pinfunction "A1_1") (pintype "passive"))
      (node (ref "D2") (pin "2") (pinfunction "A2_2") (pintype "passive"))
      (node (ref "JP5") (pin "2") (pinfunction "2_2") (pintype "passive"))
      (node (ref "R41") (pin "1") (pinfunction "1_1") (pintype "passive"))
      (node (ref "R42") (pin "1") (pinfunction "1_1") (pintype "passive"))
      (node (ref "R52") (pin "1") (pinfunction "1_1") (pintype "passive"))
      (node (ref "TB2") (pin "2") (pinfunction "2_2") (pintype "passive"))
    )
    (net (code "30") (name "VPOUT") (class "Default")
      (node (ref "C20") (pin "1") (pinfunction "1_1") (pintype "passive"))
      (node (ref "C21") (pin "1") (pinfunction "1_1") (pintype "passive"))
      (node (ref "C24") (pin "2") (pinfunction "2_2") (pintype "passive"))
      (node (ref "D1") (pin "1") (pinfunction "A1_1") (pintype "passive"))
      (node (ref "D1") (pin "2") (pinfunction "A2_2") (pintype "passive"))
      (node (ref "R39") (pin "2") (pinfunction "2_2") (pintype "passive"))
      (node (ref "R43") (pin "1") (pinfunction "1_1") (pintype "passive"))
      (node (ref "R45") (pin "1") (pinfunction "1_1") (pintype "passive"))
      (node (ref "SW6") (pin "1") (pinfunction "1_1") (pintype "passive"))
      (node (ref "TB1") (pin "2") (pinfunction "2_2") (pintype "passive"))
    )
    (net (code "31") (name "unconnected-(D3-PadNC)") (class "Default")
      (node (ref "D3") (pin "NC") (pinfunction "NC_NC") (pintype "tri_state"))
    )
  )
)
